# Rocky_Switch_v2.net
KiCad netlist of a schematic drawn in EAGLE
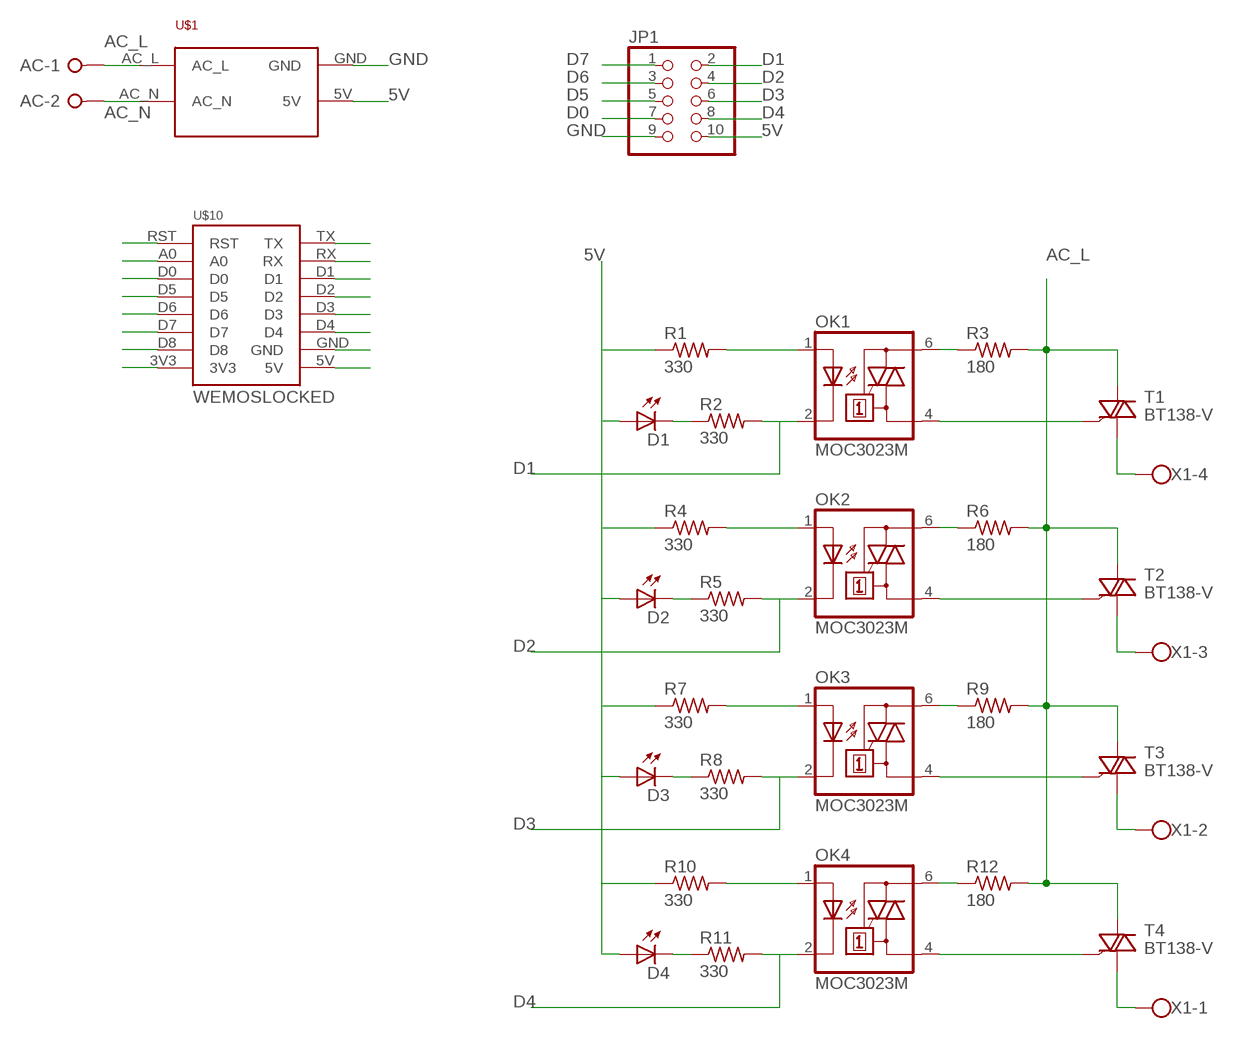
[diagram p0: schematic, sheet 1]

(export (version "E")
  (design (tool "Eeschema 10.0.6"))
  (components
    (comp (ref "AC")
      (value "W237-02P")
      (footprint "eagle-import:W237-132")
      (libsource (lib "eagle-import") (part "W237-02P"))
    )
    (comp (ref "D1")
      (value "LED3MM")
      (footprint "eagle-import:LED3MM")
      (libsource (lib "eagle-import") (part "LED3MM"))
    )
    (comp (ref "D2")
      (value "LED3MM")
      (footprint "eagle-import:LED3MM")
      (libsource (lib "eagle-import") (part "LED3MM"))
    )
    (comp (ref "D3")
      (value "LED3MM")
      (footprint "eagle-import:LED3MM")
      (libsource (lib "eagle-import") (part "LED3MM"))
    )
    (comp (ref "D4")
      (value "LED3MM")
      (footprint "eagle-import:LED3MM")
      (libsource (lib "eagle-import") (part "LED3MM"))
    )
    (comp (ref "JP1")
      (value "PINHD-2X5")
      (footprint "eagle-import:2X05")
      (libsource (lib "eagle-import") (part "PINHD-2X5"))
    )
    (comp (ref "OK1")
      (value "MOC3023M")
      (footprint "eagle-import:DIL06")
      (libsource (lib "eagle-import") (part "MOC30M23"))
    )
    (comp (ref "OK2")
      (value "MOC3023M")
      (footprint "eagle-import:DIL06")
      (libsource (lib "eagle-import") (part "MOC30M23"))
    )
    (comp (ref "OK3")
      (value "MOC3023M")
      (footprint "eagle-import:DIL06")
      (libsource (lib "eagle-import") (part "MOC30M23"))
    )
    (comp (ref "OK4")
      (value "MOC3023M")
      (footprint "eagle-import:DIL06")
      (libsource (lib "eagle-import") (part "MOC30M23"))
    )
    (comp (ref "R1")
      (value "330")
      (footprint "eagle-import:0204_7")
      (libsource (lib "eagle-import") (part "R-US_0204/7"))
    )
    (comp (ref "R2")
      (value "330")
      (footprint "eagle-import:0204_7")
      (libsource (lib "eagle-import") (part "R-US_0204/7"))
    )
    (comp (ref "R3")
      (value "180")
      (footprint "eagle-import:0204_7")
      (libsource (lib "eagle-import") (part "R-US_0204/7"))
    )
    (comp (ref "R4")
      (value "330")
      (footprint "eagle-import:0204_7")
      (libsource (lib "eagle-import") (part "R-US_0204/7"))
    )
    (comp (ref "R5")
      (value "330")
      (footprint "eagle-import:0204_7")
      (libsource (lib "eagle-import") (part "R-US_0204/7"))
    )
    (comp (ref "R6")
      (value "180")
      (footprint "eagle-import:0204_7")
      (libsource (lib "eagle-import") (part "R-US_0204/7"))
    )
    (comp (ref "R7")
      (value "330")
      (footprint "eagle-import:0204_7")
      (libsource (lib "eagle-import") (part "R-US_0204/7"))
    )
    (comp (ref "R8")
      (value "330")
      (footprint "eagle-import:0204_7")
      (libsource (lib "eagle-import") (part "R-US_0204/7"))
    )
    (comp (ref "R9")
      (value "180")
      (footprint "eagle-import:0204_7")
      (libsource (lib "eagle-import") (part "R-US_0204/7"))
    )
    (comp (ref "R10")
      (value "330")
      (footprint "eagle-import:0204_7")
      (libsource (lib "eagle-import") (part "R-US_0204/7"))
    )
    (comp (ref "R11")
      (value "330")
      (footprint "eagle-import:0204_7")
      (libsource (lib "eagle-import") (part "R-US_0204/7"))
    )
    (comp (ref "R12")
      (value "180")
      (footprint "eagle-import:0204_7")
      (libsource (lib "eagle-import") (part "R-US_0204/7"))
    )
    (comp (ref "T1")
      (value "BT138-V")
      (footprint "eagle-import:TO220BV")
      (libsource (lib "eagle-import") (part "BT138-V"))
    )
    (comp (ref "T2")
      (value "BT138-V")
      (footprint "eagle-import:TO220BV")
      (libsource (lib "eagle-import") (part "BT138-V"))
    )
    (comp (ref "T3")
      (value "BT138-V")
      (footprint "eagle-import:TO220BV")
      (libsource (lib "eagle-import") (part "BT138-V"))
    )
    (comp (ref "T4")
      (value "BT138-V")
      (footprint "eagle-import:TO220BV")
      (libsource (lib "eagle-import") (part "BT138-V"))
    )
    (comp (ref "U$1")
      (value "POWER_SUPPLY_220VAC_5V")
      (footprint "eagle-import:POWER_SUPPLY_220VAC_5V")
      (libsource (lib "eagle-import") (part "POWER_SUPPLY_220VAC_5V"))
    )
    (comp (ref "U$10")
      (value "WEMOSLOCKED")
      (footprint "eagle-import:WEMOS_LOCKED")
      (libsource (lib "eagle-import") (part "WEMOSLOCKED"))
    )
    (comp (ref "X1")
      (value "W237-4")
      (footprint "eagle-import:W237-4")
      (libsource (lib "eagle-import") (part "W237-4"))
    )
  )
  (nets
    (net (code "1") (name "/5V") (class "Default")
      (node (ref "D1") (pin "A") (pinfunction "A_A") (pintype "passive"))
      (node (ref "D2") (pin "A") (pinfunction "A_A") (pintype "passive"))
      (node (ref "D3") (pin "A") (pinfunction "A_A") (pintype "passive"))
      (node (ref "D4") (pin "A") (pinfunction "A_A") (pintype "passive"))
      (node (ref "JP1") (pin "10") (pinfunction "10_10") (pintype "passive"))
      (node (ref "R1") (pin "1") (pinfunction "1_1") (pintype "passive"))
      (node (ref "R10") (pin "1") (pinfunction "1_1") (pintype "passive"))
      (node (ref "R4") (pin "1") (pinfunction "1_1") (pintype "passive"))
      (node (ref "R7") (pin "1") (pinfunction "1_1") (pintype "passive"))
      (node (ref "U$1") (pin "5V") (pinfunction "5V_5V") (pintype "bidirectional"))
      (node (ref "U$10") (pin "5V") (pinfunction "5V_5V") (pintype "bidirectional"))
    )
    (net (code "2") (name "/AC_L") (class "Default")
      (node (ref "AC") (pin "1") (pinfunction "KL_1") (pintype "passive"))
      (node (ref "R12") (pin "2") (pinfunction "2_2") (pintype "passive"))
      (node (ref "R3") (pin "2") (pinfunction "2_2") (pintype "passive"))
      (node (ref "R6") (pin "2") (pinfunction "2_2") (pintype "passive"))
      (node (ref "R9") (pin "2") (pinfunction "2_2") (pintype "passive"))
      (node (ref "T1") (pin "T2") (pinfunction "A2_T2") (pintype "passive"))
      (node (ref "T2") (pin "T2") (pinfunction "A2_T2") (pintype "passive"))
      (node (ref "T3") (pin "T2") (pinfunction "A2_T2") (pintype "passive"))
      (node (ref "T4") (pin "T2") (pinfunction "A2_T2") (pintype "passive"))
      (node (ref "U$1") (pin "AC_L") (pinfunction "AC_L_AC_L") (pintype "bidirectional"))
    )
    (net (code "3") (name "/AC_N") (class "Default")
      (node (ref "AC") (pin "2") (pinfunction "KL_2") (pintype "passive"))
      (node (ref "U$1") (pin "AC_N") (pinfunction "AC_N_AC_N") (pintype "bidirectional"))
    )
    (net (code "4") (name "/D0") (class "Default")
      (node (ref "JP1") (pin "7") (pinfunction "7_7") (pintype "passive"))
      (node (ref "U$10") (pin "D0") (pinfunction "D0_D0") (pintype "bidirectional"))
    )
    (net (code "5") (name "/D1") (class "Default")
      (node (ref "JP1") (pin "2") (pinfunction "2_2") (pintype "passive"))
      (node (ref "OK1") (pin "2") (pinfunction "C_2") (pintype "passive"))
      (node (ref "R2") (pin "2") (pinfunction "2_2") (pintype "passive"))
      (node (ref "U$10") (pin "D1") (pinfunction "D1_D1") (pintype "bidirectional"))
    )
    (net (code "6") (name "/D2") (class "Default")
      (node (ref "JP1") (pin "4") (pinfunction "4_4") (pintype "passive"))
      (node (ref "OK2") (pin "2") (pinfunction "C_2") (pintype "passive"))
      (node (ref "R5") (pin "2") (pinfunction "2_2") (pintype "passive"))
      (node (ref "U$10") (pin "D2") (pinfunction "D2_D2") (pintype "bidirectional"))
    )
    (net (code "7") (name "/D3") (class "Default")
      (node (ref "JP1") (pin "6") (pinfunction "6_6") (pintype "passive"))
      (node (ref "OK3") (pin "2") (pinfunction "C_2") (pintype "passive"))
      (node (ref "R8") (pin "2") (pinfunction "2_2") (pintype "passive"))
      (node (ref "U$10") (pin "D3") (pinfunction "D3_D3") (pintype "bidirectional"))
    )
    (net (code "8") (name "/D4") (class "Default")
      (node (ref "JP1") (pin "8") (pinfunction "8_8") (pintype "passive"))
      (node (ref "OK4") (pin "2") (pinfunction "C_2") (pintype "passive"))
      (node (ref "R11") (pin "2") (pinfunction "2_2") (pintype "passive"))
      (node (ref "U$10") (pin "D4") (pinfunction "D4_D4") (pintype "bidirectional"))
    )
    (net (code "9") (name "/D5") (class "Default")
      (node (ref "JP1") (pin "5") (pinfunction "5_5") (pintype "passive"))
      (node (ref "U$10") (pin "D5") (pinfunction "D5_D5") (pintype "bidirectional"))
    )
    (net (code "10") (name "/D6") (class "Default")
      (node (ref "JP1") (pin "3") (pinfunction "3_3") (pintype "passive"))
      (node (ref "U$10") (pin "D6") (pinfunction "D6_D6") (pintype "bidirectional"))
    )
    (net (code "11") (name "/D7") (class "Default")
      (node (ref "JP1") (pin "1") (pinfunction "1_1") (pintype "passive"))
      (node (ref "U$10") (pin "D7") (pinfunction "D7_D7") (pintype "bidirectional"))
    )
    (net (code "12") (name "/GND") (class "Default")
      (node (ref "JP1") (pin "9") (pinfunction "9_9") (pintype "passive"))
      (node (ref "U$1") (pin "GND") (pinfunction "GND_GND") (pintype "bidirectional"))
      (node (ref "U$10") (pin "GND") (pinfunction "GND_GND") (pintype "bidirectional"))
    )
    (net (code "13") (name "Net-(D1-C)") (class "Default")
      (node (ref "D1") (pin "K") (pinfunction "C_K") (pintype "passive"))
      (node (ref "R2") (pin "1") (pinfunction "1_1") (pintype "passive"))
    )
    (net (code "14") (name "Net-(D2-C)") (class "Default")
      (node (ref "D2") (pin "K") (pinfunction "C_K") (pintype "passive"))
      (node (ref "R5") (pin "1") (pinfunction "1_1") (pintype "passive"))
    )
    (net (code "15") (name "Net-(D3-C)") (class "Default")
      (node (ref "D3") (pin "K") (pinfunction "C_K") (pintype "passive"))
      (node (ref "R8") (pin "1") (pinfunction "1_1") (pintype "passive"))
    )
    (net (code "16") (name "Net-(D4-C)") (class "Default")
      (node (ref "D4") (pin "K") (pinfunction "C_K") (pintype "passive"))
      (node (ref "R11") (pin "1") (pinfunction "1_1") (pintype "passive"))
    )
    (net (code "17") (name "Net-(OK1-A)") (class "Default")
      (node (ref "OK1") (pin "1") (pinfunction "A_1") (pintype "passive"))
      (node (ref "R1") (pin "2") (pinfunction "2_2") (pintype "passive"))
    )
    (net (code "18") (name "Net-(OK1-A1)") (class "Default")
      (node (ref "OK1") (pin "4") (pinfunction "A1_4") (pintype "passive"))
      (node (ref "T1") (pin "G") (pinfunction "G_G") (pintype "passive"))
    )
    (net (code "19") (name "Net-(OK1-A2)") (class "Default")
      (node (ref "OK1") (pin "6") (pinfunction "A2_6") (pintype "passive"))
      (node (ref "R3") (pin "1") (pinfunction "1_1") (pintype "passive"))
    )
    (net (code "20") (name "Net-(OK2-A)") (class "Default")
      (node (ref "OK2") (pin "1") (pinfunction "A_1") (pintype "passive"))
      (node (ref "R4") (pin "2") (pinfunction "2_2") (pintype "passive"))
    )
    (net (code "21") (name "Net-(OK2-A1)") (class "Default")
      (node (ref "OK2") (pin "4") (pinfunction "A1_4") (pintype "passive"))
      (node (ref "T2") (pin "G") (pinfunction "G_G") (pintype "passive"))
    )
    (net (code "22") (name "Net-(OK2-A2)") (class "Default")
      (node (ref "OK2") (pin "6") (pinfunction "A2_6") (pintype "passive"))
      (node (ref "R6") (pin "1") (pinfunction "1_1") (pintype "passive"))
    )
    (net (code "23") (name "Net-(OK3-A)") (class "Default")
      (node (ref "OK3") (pin "1") (pinfunction "A_1") (pintype "passive"))
      (node (ref "R7") (pin "2") (pinfunction "2_2") (pintype "passive"))
    )
    (net (code "24") (name "Net-(OK3-A1)") (class "Default")
      (node (ref "OK3") (pin "4") (pinfunction "A1_4") (pintype "passive"))
      (node (ref "T3") (pin "G") (pinfunction "G_G") (pintype "passive"))
    )
    (net (code "25") (name "Net-(OK3-A2)") (class "Default")
      (node (ref "OK3") (pin "6") (pinfunction "A2_6") (pintype "passive"))
      (node (ref "R9") (pin "1") (pinfunction "1_1") (pintype "passive"))
    )
    (net (code "26") (name "Net-(OK4-A)") (class "Default")
      (node (ref "OK4") (pin "1") (pinfunction "A_1") (pintype "passive"))
      (node (ref "R10") (pin "2") (pinfunction "2_2") (pintype "passive"))
    )
    (net (code "27") (name "Net-(OK4-A1)") (class "Default")
      (node (ref "OK4") (pin "4") (pinfunction "A1_4") (pintype "passive"))
      (node (ref "T4") (pin "G") (pinfunction "G_G") (pintype "passive"))
    )
    (net (code "28") (name "Net-(OK4-A2)") (class "Default")
      (node (ref "OK4") (pin "6") (pinfunction "A2_6") (pintype "passive"))
      (node (ref "R12") (pin "1") (pinfunction "1_1") (pintype "passive"))
    )
    (net (code "29") (name "Net-(T1-A1)") (class "Default")
      (node (ref "T1") (pin "T1") (pinfunction "A1_T1") (pintype "passive"))
      (node (ref "X1") (pin "4") (pinfunction "KL_4") (pintype "passive"))
    )
    (net (code "30") (name "Net-(T2-A1)") (class "Default")
      (node (ref "T2") (pin "T1") (pinfunction "A1_T1") (pintype "passive"))
      (node (ref "X1") (pin "3") (pinfunction "KL_3") (pintype "passive"))
    )
    (net (code "31") (name "Net-(T3-A1)") (class "Default")
      (node (ref "T3") (pin "T1") (pinfunction "A1_T1") (pintype "passive"))
      (node (ref "X1") (pin "2") (pinfunction "KL_2") (pintype "passive"))
    )
    (net (code "32") (name "Net-(T4-A1)") (class "Default")
      (node (ref "T4") (pin "T1") (pinfunction "A1_T1") (pintype "passive"))
      (node (ref "X1") (pin "1") (pinfunction "KL_1") (pintype "passive"))
    )
    (net (code "33") (name "unconnected-(U$10-Pad3V3)") (class "Default")
      (node (ref "U$10") (pin "3V3") (pinfunction "3V3_3V3") (pintype "bidirectional"))
    )
    (net (code "34") (name "unconnected-(U$10-PadA0)") (class "Default")
      (node (ref "U$10") (pin "A0") (pinfunction "A0_A0") (pintype "bidirectional"))
    )
    (net (code "35") (name "unconnected-(U$10-PadD8)") (class "Default")
      (node (ref "U$10") (pin "D8") (pinfunction "D8_D8") (pintype "bidirectional"))
    )
    (net (code "36") (name "unconnected-(U$10-PadRST)") (class "Default")
      (node (ref "U$10") (pin "RST") (pinfunction "RST_RST") (pintype "bidirectional"))
    )
    (net (code "37") (name "unconnected-(U$10-PadRX)") (class "Default")
      (node (ref "U$10") (pin "RX") (pinfunction "RX_RX") (pintype "bidirectional"))
    )
    (net (code "38") (name "unconnected-(U$10-PadTX)") (class "Default")
      (node (ref "U$10") (pin "TX") (pinfunction "TX_TX") (pintype "bidirectional"))
    )
  )
)
